# EncoderDebouncer.net
KiCad netlist of a schematic drawn in Altium Designer
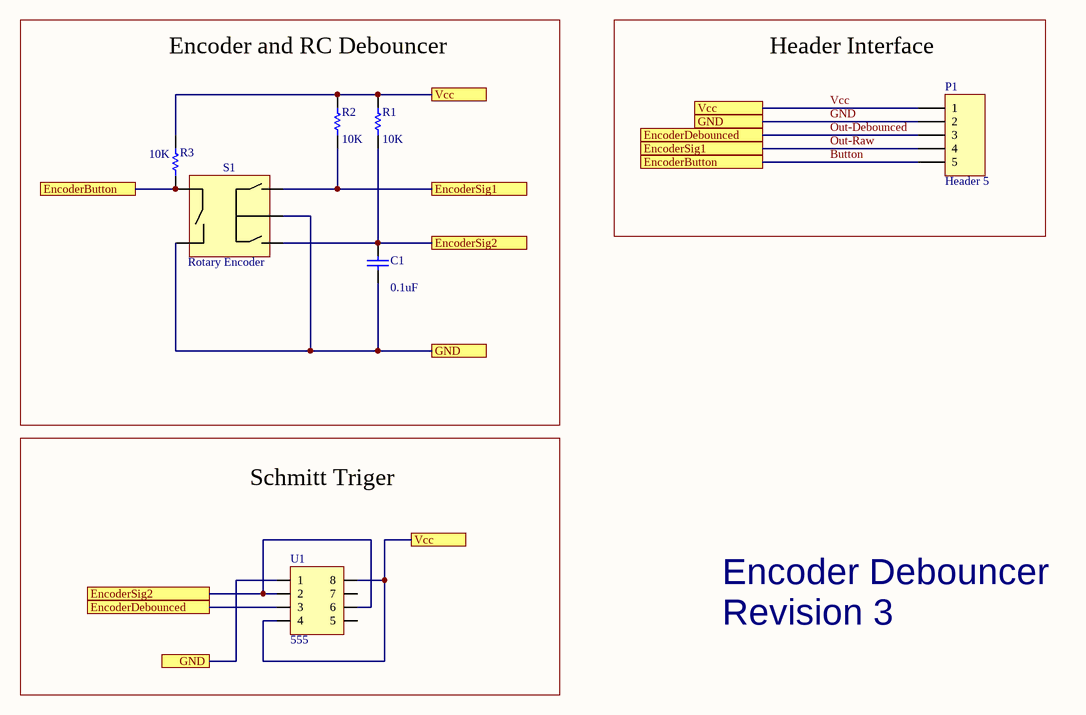
[diagram p0: EncoderDebouncer.SchDoc]

(export (version "E")
  (design (tool "Eeschema 10.0.6"))
  (components
    (comp (ref "C1")
      (value "0.1uF")
      (footprint "0805-CAP")
      (description "Capacitor")
      (fields (field (name "Comment") "Cap") (field (name "PUBLISHER") "Altium Limited"))
      (libsource (lib "Miscellaneous Devices") (part "Cap"))
    )
    (comp (ref "P1")
      (value "Header 5")
      (footprint "Pin Header 1x5 TH Pitch 2.54mm")
      (description "Header, 5-Pin")
      (fields (field (name "PUBLISHER") "Altium Limited"))
      (libsource (lib "Miscellaneous Connectors") (part "Header 5"))
    )
    (comp (ref "R1")
      (value "10K")
      (footprint "0805-RES")
      (description "Resistor")
      (fields (field (name "Comment") "Res1") (field (name "PUBLISHER") "Altium Limited"))
      (libsource (lib "Miscellaneous Devices") (part "Res1"))
    )
    (comp (ref "R2")
      (value "10K")
      (footprint "0805-RES")
      (description "Resistor")
      (fields (field (name "Comment") "Res1") (field (name "PUBLISHER") "Altium Limited"))
      (libsource (lib "Miscellaneous Devices") (part "Res1"))
    )
    (comp (ref "R3")
      (value "10K")
      (footprint "0805-RES")
      (description "Resistor")
      (fields (field (name "Comment") "Res1") (field (name "PUBLISHER") "Altium Limited"))
      (libsource (lib "Miscellaneous Devices") (part "Res1"))
    )
    (comp (ref "S1")
      (value "Rotary Encoder")
      (libsource (lib "EncoderDebouncerComponents") (part "Rotary Encoder"))
    )
    (comp (ref "U1") (value "555") (libsource (lib "EncoderDebouncerComponents") (part "555")))
  )
  (nets
    (net (code "1") (name "/Button") (class "Default")
      (node (ref "P1") (pin "5") (pinfunction "5_5") (pintype "passive"))
      (node (ref "R3") (pin "1") (pinfunction "1_1") (pintype "passive"))
      (node (ref "S1") (pin "5") (pintype "passive"))
    )
    (net (code "2") (name "/EncoderSig2") (class "Default")
      (node (ref "C1") (pin "2") (pinfunction "2_2") (pintype "passive"))
      (node (ref "R1") (pin "1") (pinfunction "1_1") (pintype "passive"))
      (node (ref "S1") (pin "3") (pintype "passive"))
      (node (ref "U1") (pin "2") (pinfunction "2_2") (pintype "passive"))
      (node (ref "U1") (pin "6") (pinfunction "6_6") (pintype "passive"))
    )
    (net (code "3") (name "/GND") (class "Default")
      (node (ref "C1") (pin "1") (pinfunction "1_1") (pintype "passive"))
      (node (ref "P1") (pin "2") (pinfunction "2_2") (pintype "passive"))
      (node (ref "S1") (pin "2") (pintype "passive"))
      (node (ref "S1") (pin "4") (pintype "passive"))
      (node (ref "U1") (pin "1") (pinfunction "1_1") (pintype "passive"))
    )
    (net (code "4") (name "/Out-Debounced") (class "Default")
      (node (ref "P1") (pin "3") (pinfunction "3_3") (pintype "passive"))
      (node (ref "U1") (pin "3") (pinfunction "3_3") (pintype "passive"))
    )
    (net (code "5") (name "/Out-Raw") (class "Default")
      (node (ref "P1") (pin "4") (pinfunction "4_4") (pintype "passive"))
      (node (ref "R2") (pin "1") (pinfunction "1_1") (pintype "passive"))
      (node (ref "S1") (pin "1") (pintype "passive"))
    )
    (net (code "6") (name "/Vcc") (class "Default")
      (node (ref "P1") (pin "1") (pinfunction "1_1") (pintype "passive"))
      (node (ref "R1") (pin "2") (pinfunction "2_2") (pintype "passive"))
      (node (ref "R2") (pin "2") (pinfunction "2_2") (pintype "passive"))
      (node (ref "R3") (pin "2") (pinfunction "2_2") (pintype "passive"))
      (node (ref "U1") (pin "4") (pinfunction "4_4") (pintype "passive"))
      (node (ref "U1") (pin "8") (pinfunction "8_8") (pintype "passive"))
    )
    (net (code "7") (name "unconnected-(U1-Pad5)") (class "Default")
      (node (ref "U1") (pin "5") (pinfunction "5_5") (pintype "passive"))
    )
    (net (code "8") (name "unconnected-(U1-Pad7)") (class "Default")
      (node (ref "U1") (pin "7") (pinfunction "7_7") (pintype "passive"))
    )
  )
)
